# SCH_Mouse-pad_2025-08-08.net
KiCad netlist of a schematic drawn in EasyEDA
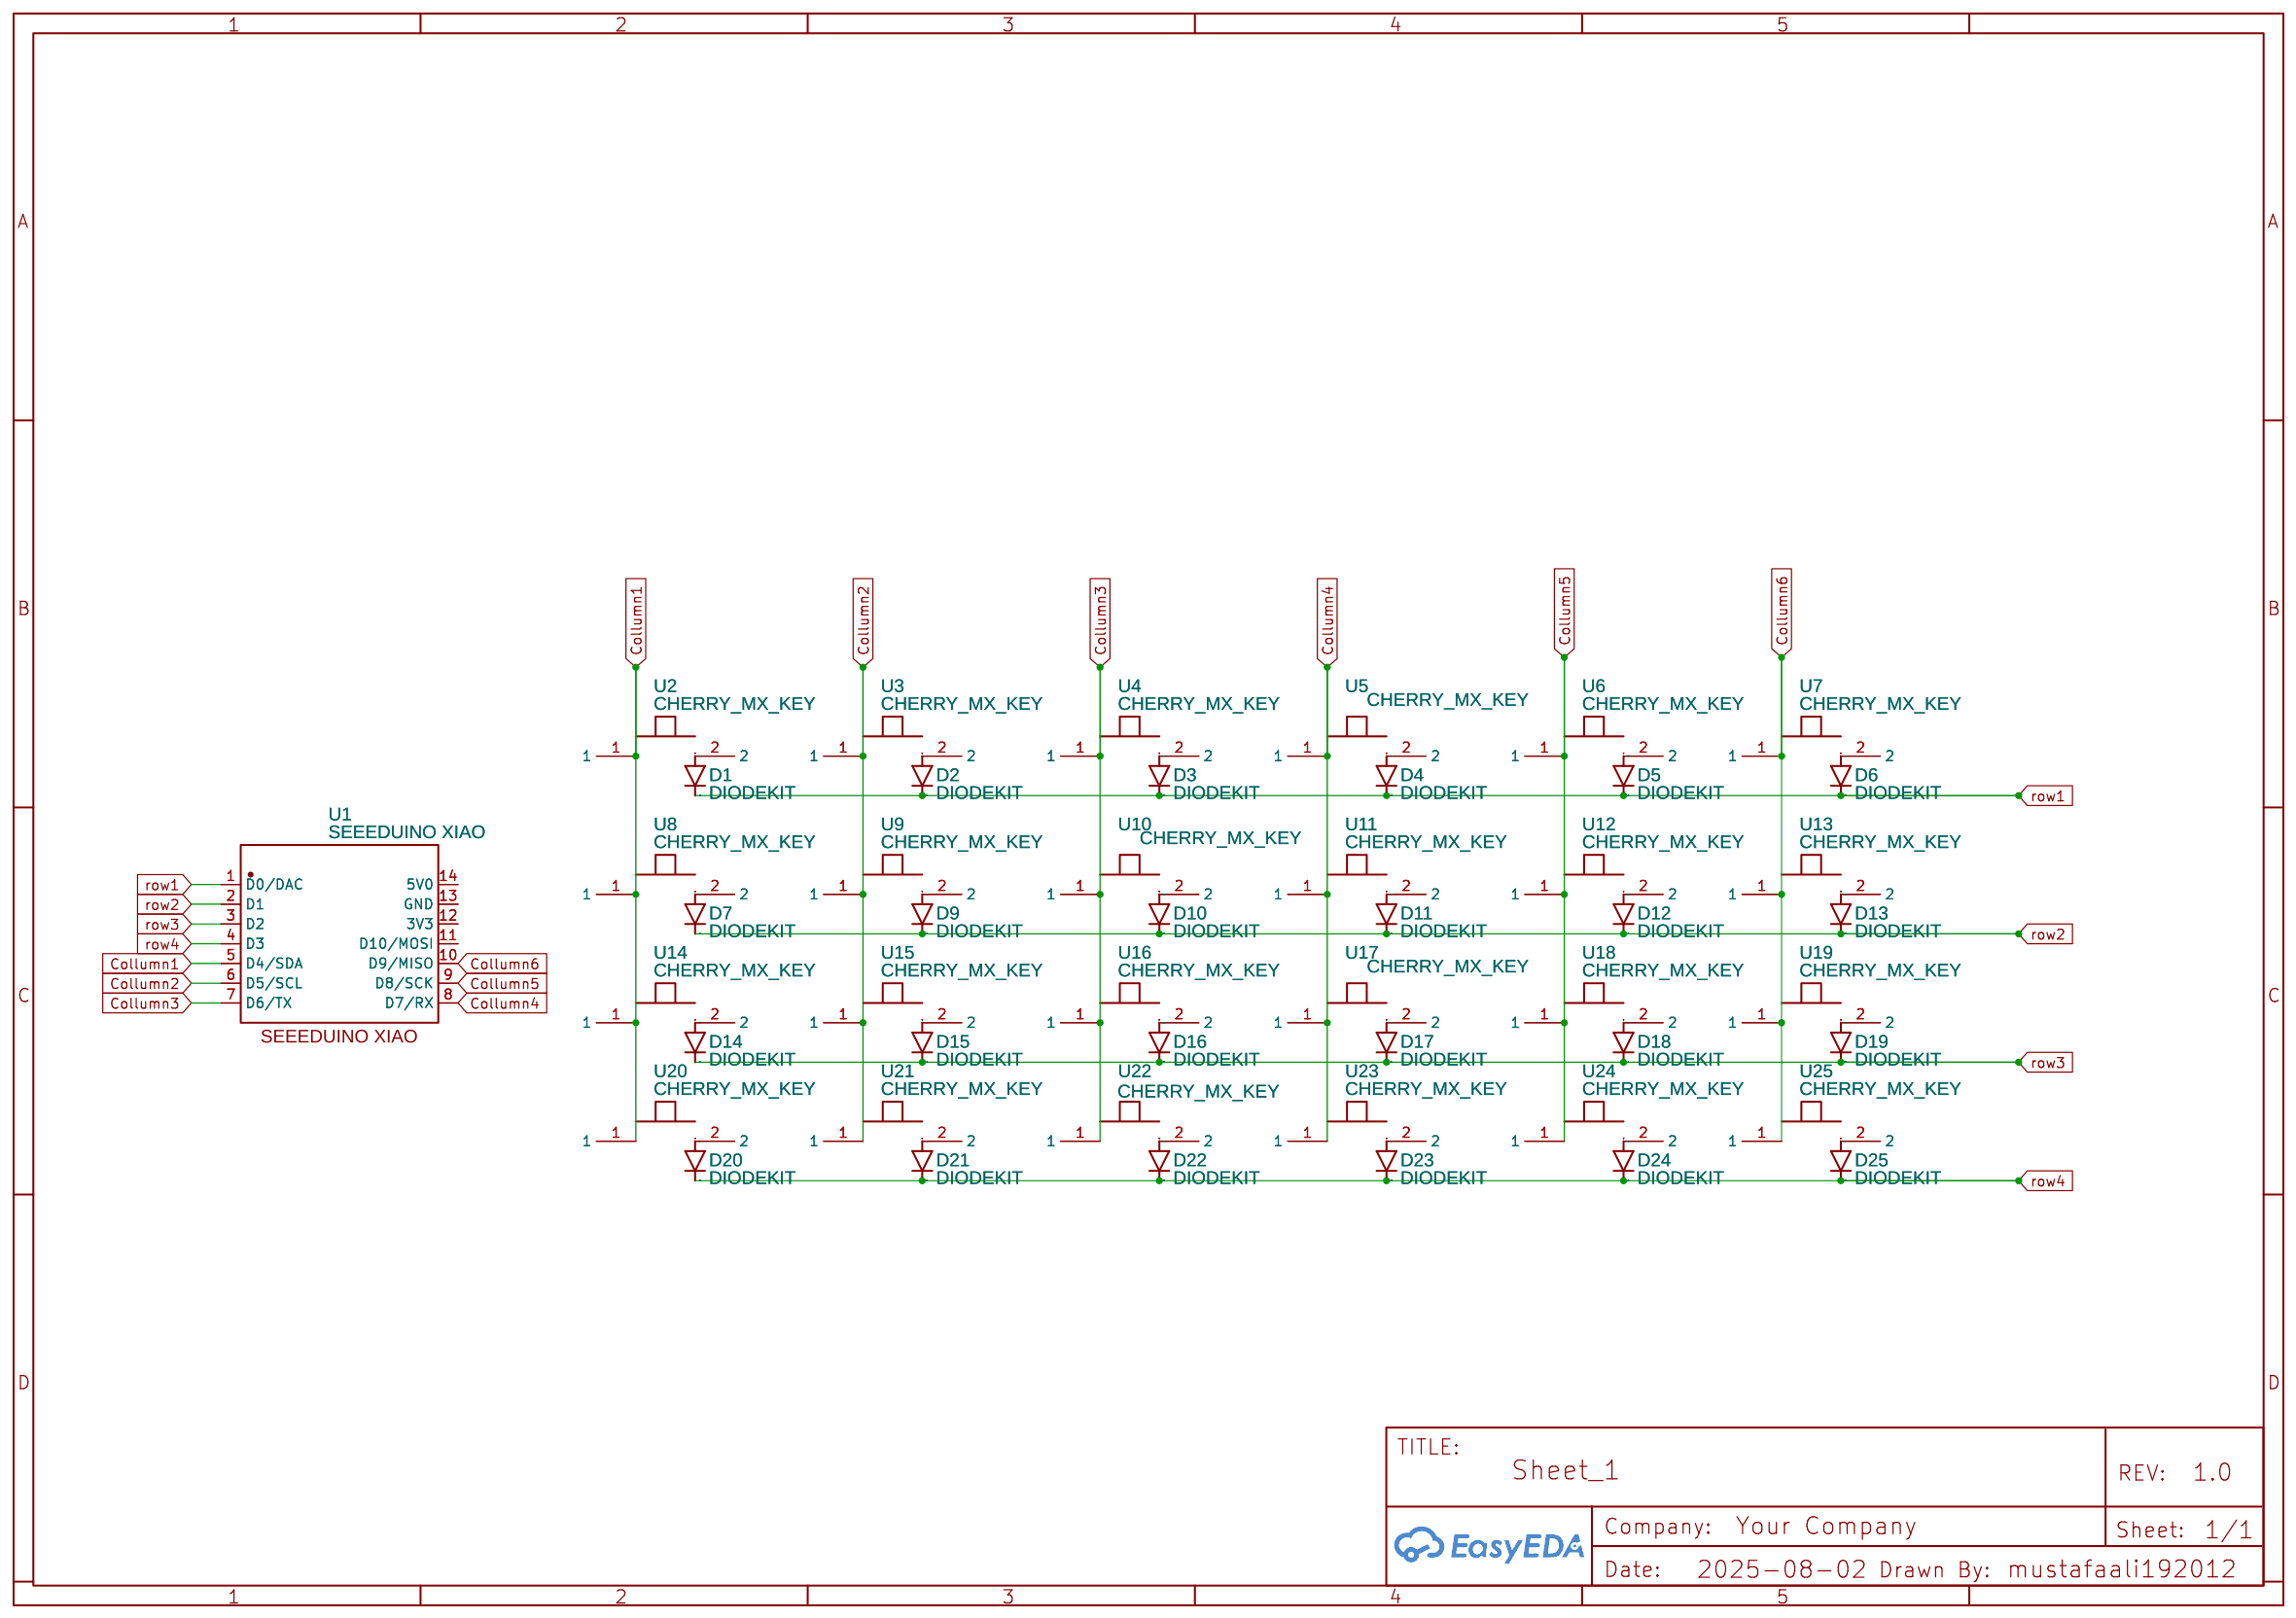
[diagram p0: schematic sheet]

(export (version "E")
  (design (tool "Eeschema 10.0.6"))
  (components
    (comp (ref "D1") (value "DIODEKIT") (libsource (lib "") (part "DIODEKIT")))
    (comp (ref "D2") (value "DIODEKIT") (libsource (lib "") (part "DIODEKIT")))
    (comp (ref "D3") (value "DIODEKIT") (libsource (lib "") (part "DIODEKIT")))
    (comp (ref "D4") (value "DIODEKIT") (libsource (lib "") (part "DIODEKIT")))
    (comp (ref "D5") (value "DIODEKIT") (libsource (lib "") (part "DIODEKIT")))
    (comp (ref "D6") (value "DIODEKIT") (libsource (lib "") (part "DIODEKIT")))
    (comp (ref "D7") (value "DIODEKIT") (libsource (lib "") (part "DIODEKIT")))
    (comp (ref "D9") (value "DIODEKIT") (libsource (lib "") (part "DIODEKIT")))
    (comp (ref "D10") (value "DIODEKIT") (libsource (lib "") (part "DIODEKIT")))
    (comp (ref "D11") (value "DIODEKIT") (libsource (lib "") (part "DIODEKIT")))
    (comp (ref "D12") (value "DIODEKIT") (libsource (lib "") (part "DIODEKIT")))
    (comp (ref "D13") (value "DIODEKIT") (libsource (lib "") (part "DIODEKIT")))
    (comp (ref "D14") (value "DIODEKIT") (libsource (lib "") (part "DIODEKIT")))
    (comp (ref "D15") (value "DIODEKIT") (libsource (lib "") (part "DIODEKIT")))
    (comp (ref "D16") (value "DIODEKIT") (libsource (lib "") (part "DIODEKIT")))
    (comp (ref "D17") (value "DIODEKIT") (libsource (lib "") (part "DIODEKIT")))
    (comp (ref "D18") (value "DIODEKIT") (libsource (lib "") (part "DIODEKIT")))
    (comp (ref "D19") (value "DIODEKIT") (libsource (lib "") (part "DIODEKIT")))
    (comp (ref "D20") (value "DIODEKIT") (libsource (lib "") (part "DIODEKIT")))
    (comp (ref "D21") (value "DIODEKIT") (libsource (lib "") (part "DIODEKIT")))
    (comp (ref "D22") (value "DIODEKIT") (libsource (lib "") (part "DIODEKIT")))
    (comp (ref "D23") (value "DIODEKIT") (libsource (lib "") (part "DIODEKIT")))
    (comp (ref "D24") (value "DIODEKIT") (libsource (lib "") (part "DIODEKIT")))
    (comp (ref "D25") (value "DIODEKIT") (libsource (lib "") (part "DIODEKIT")))
    (comp (ref "U1")
      (value "SEEEDUINO XIAO")
      (fields (field (name "Manufacturer") "Seeeduino"))
      (libsource (lib "") (part "SEEEDUINO XIAO"))
    )
    (comp (ref "U2") (value "CHERRY_MX_KEY") (libsource (lib "") (part "CHERRY_MX_KEY")))
    (comp (ref "U3") (value "CHERRY_MX_KEY") (libsource (lib "") (part "CHERRY_MX_KEY")))
    (comp (ref "U4") (value "CHERRY_MX_KEY") (libsource (lib "") (part "CHERRY_MX_KEY")))
    (comp (ref "U5") (value "CHERRY_MX_KEY") (libsource (lib "") (part "CHERRY_MX_KEY")))
    (comp (ref "U6") (value "CHERRY_MX_KEY") (libsource (lib "") (part "CHERRY_MX_KEY")))
    (comp (ref "U7") (value "CHERRY_MX_KEY") (libsource (lib "") (part "CHERRY_MX_KEY")))
    (comp (ref "U8") (value "CHERRY_MX_KEY") (libsource (lib "") (part "CHERRY_MX_KEY")))
    (comp (ref "U9") (value "CHERRY_MX_KEY") (libsource (lib "") (part "CHERRY_MX_KEY")))
    (comp (ref "U10") (value "CHERRY_MX_KEY") (libsource (lib "") (part "CHERRY_MX_KEY")))
    (comp (ref "U11") (value "CHERRY_MX_KEY") (libsource (lib "") (part "CHERRY_MX_KEY")))
    (comp (ref "U12") (value "CHERRY_MX_KEY") (libsource (lib "") (part "CHERRY_MX_KEY")))
    (comp (ref "U13") (value "CHERRY_MX_KEY") (libsource (lib "") (part "CHERRY_MX_KEY")))
    (comp (ref "U14") (value "CHERRY_MX_KEY") (libsource (lib "") (part "CHERRY_MX_KEY")))
    (comp (ref "U15") (value "CHERRY_MX_KEY") (libsource (lib "") (part "CHERRY_MX_KEY")))
    (comp (ref "U16") (value "CHERRY_MX_KEY") (libsource (lib "") (part "CHERRY_MX_KEY")))
    (comp (ref "U17") (value "CHERRY_MX_KEY") (libsource (lib "") (part "CHERRY_MX_KEY")))
    (comp (ref "U18") (value "CHERRY_MX_KEY") (libsource (lib "") (part "CHERRY_MX_KEY")))
    (comp (ref "U19") (value "CHERRY_MX_KEY") (libsource (lib "") (part "CHERRY_MX_KEY")))
    (comp (ref "U20") (value "CHERRY_MX_KEY") (libsource (lib "") (part "CHERRY_MX_KEY")))
    (comp (ref "U21") (value "CHERRY_MX_KEY") (libsource (lib "") (part "CHERRY_MX_KEY")))
    (comp (ref "U22") (value "CHERRY_MX_KEY") (libsource (lib "") (part "CHERRY_MX_KEY")))
    (comp (ref "U23") (value "CHERRY_MX_KEY") (libsource (lib "") (part "CHERRY_MX_KEY")))
    (comp (ref "U24") (value "CHERRY_MX_KEY") (libsource (lib "") (part "CHERRY_MX_KEY")))
    (comp (ref "U25") (value "CHERRY_MX_KEY") (libsource (lib "") (part "CHERRY_MX_KEY")))
  )
  (nets
    (net (code "1") (name "Collumn1") (class "Default")
      (node (ref "U1") (pin "5") (pinfunction "D4/SDA_5") (pintype "unspecified"))
      (node (ref "U14") (pin "1") (pinfunction "1_1") (pintype "unspecified"))
      (node (ref "U2") (pin "1") (pinfunction "1_1") (pintype "unspecified"))
      (node (ref "U20") (pin "1") (pinfunction "1_1") (pintype "unspecified"))
      (node (ref "U8") (pin "1") (pinfunction "1_1") (pintype "unspecified"))
    )
    (net (code "2") (name "Collumn2") (class "Default")
      (node (ref "U1") (pin "6") (pinfunction "D5/SCL_6") (pintype "unspecified"))
      (node (ref "U15") (pin "1") (pinfunction "1_1") (pintype "unspecified"))
      (node (ref "U21") (pin "1") (pinfunction "1_1") (pintype "unspecified"))
      (node (ref "U3") (pin "1") (pinfunction "1_1") (pintype "unspecified"))
      (node (ref "U9") (pin "1") (pinfunction "1_1") (pintype "unspecified"))
    )
    (net (code "3") (name "Collumn3") (class "Default")
      (node (ref "U1") (pin "7") (pinfunction "D6/TX_7") (pintype "unspecified"))
      (node (ref "U10") (pin "1") (pinfunction "1_1") (pintype "unspecified"))
      (node (ref "U16") (pin "1") (pinfunction "1_1") (pintype "unspecified"))
      (node (ref "U22") (pin "1") (pinfunction "1_1") (pintype "unspecified"))
      (node (ref "U4") (pin "1") (pinfunction "1_1") (pintype "unspecified"))
    )
    (net (code "4") (name "Collumn4") (class "Default")
      (node (ref "U1") (pin "8") (pinfunction "D7/RX_8") (pintype "unspecified"))
      (node (ref "U11") (pin "1") (pinfunction "1_1") (pintype "unspecified"))
      (node (ref "U17") (pin "1") (pinfunction "1_1") (pintype "unspecified"))
      (node (ref "U23") (pin "1") (pinfunction "1_1") (pintype "unspecified"))
      (node (ref "U5") (pin "1") (pinfunction "1_1") (pintype "unspecified"))
    )
    (net (code "5") (name "Collumn5") (class "Default")
      (node (ref "U1") (pin "9") (pinfunction "D8/SCK_9") (pintype "unspecified"))
      (node (ref "U12") (pin "1") (pinfunction "1_1") (pintype "unspecified"))
      (node (ref "U18") (pin "1") (pinfunction "1_1") (pintype "unspecified"))
      (node (ref "U24") (pin "1") (pinfunction "1_1") (pintype "unspecified"))
      (node (ref "U6") (pin "1") (pinfunction "1_1") (pintype "unspecified"))
    )
    (net (code "6") (name "Collumn6") (class "Default")
      (node (ref "U1") (pin "10") (pinfunction "D9/MISO_10") (pintype "unspecified"))
      (node (ref "U13") (pin "1") (pinfunction "1_1") (pintype "unspecified"))
      (node (ref "U19") (pin "1") (pinfunction "1_1") (pintype "unspecified"))
      (node (ref "U25") (pin "1") (pinfunction "1_1") (pintype "unspecified"))
      (node (ref "U7") (pin "1") (pinfunction "1_1") (pintype "unspecified"))
    )
    (net (code "7") (name "Net-(D1-PadA)") (class "Default")
      (node (ref "D1") (pin "A") (pinfunction "A_A") (pintype "bidirectional"))
      (node (ref "U2") (pin "2") (pinfunction "2_2") (pintype "unspecified"))
    )
    (net (code "8") (name "Net-(D2-PadA)") (class "Default")
      (node (ref "D2") (pin "A") (pinfunction "A_A") (pintype "bidirectional"))
      (node (ref "U3") (pin "2") (pinfunction "2_2") (pintype "unspecified"))
    )
    (net (code "9") (name "Net-(D3-PadA)") (class "Default")
      (node (ref "D3") (pin "A") (pinfunction "A_A") (pintype "bidirectional"))
      (node (ref "U4") (pin "2") (pinfunction "2_2") (pintype "unspecified"))
    )
    (net (code "10") (name "Net-(D4-PadA)") (class "Default")
      (node (ref "D4") (pin "A") (pinfunction "A_A") (pintype "bidirectional"))
      (node (ref "U5") (pin "2") (pinfunction "2_2") (pintype "unspecified"))
    )
    (net (code "11") (name "Net-(D5-PadA)") (class "Default")
      (node (ref "D5") (pin "A") (pinfunction "A_A") (pintype "bidirectional"))
      (node (ref "U6") (pin "2") (pinfunction "2_2") (pintype "unspecified"))
    )
    (net (code "12") (name "Net-(D6-PadA)") (class "Default")
      (node (ref "D6") (pin "A") (pinfunction "A_A") (pintype "bidirectional"))
      (node (ref "U7") (pin "2") (pinfunction "2_2") (pintype "unspecified"))
    )
    (net (code "13") (name "Net-(D7-PadA)") (class "Default")
      (node (ref "D7") (pin "A") (pinfunction "A_A") (pintype "bidirectional"))
      (node (ref "U8") (pin "2") (pinfunction "2_2") (pintype "unspecified"))
    )
    (net (code "14") (name "Net-(D9-PadA)") (class "Default")
      (node (ref "D9") (pin "A") (pinfunction "A_A") (pintype "bidirectional"))
      (node (ref "U9") (pin "2") (pinfunction "2_2") (pintype "unspecified"))
    )
    (net (code "15") (name "Net-(D10-PadA)") (class "Default")
      (node (ref "D10") (pin "A") (pinfunction "A_A") (pintype "bidirectional"))
      (node (ref "U10") (pin "2") (pinfunction "2_2") (pintype "unspecified"))
    )
    (net (code "16") (name "Net-(D11-PadA)") (class "Default")
      (node (ref "D11") (pin "A") (pinfunction "A_A") (pintype "bidirectional"))
      (node (ref "U11") (pin "2") (pinfunction "2_2") (pintype "unspecified"))
    )
    (net (code "17") (name "Net-(D12-PadA)") (class "Default")
      (node (ref "D12") (pin "A") (pinfunction "A_A") (pintype "bidirectional"))
      (node (ref "U12") (pin "2") (pinfunction "2_2") (pintype "unspecified"))
    )
    (net (code "18") (name "Net-(D13-PadA)") (class "Default")
      (node (ref "D13") (pin "A") (pinfunction "A_A") (pintype "bidirectional"))
      (node (ref "U13") (pin "2") (pinfunction "2_2") (pintype "unspecified"))
    )
    (net (code "19") (name "Net-(D14-PadA)") (class "Default")
      (node (ref "D14") (pin "A") (pinfunction "A_A") (pintype "bidirectional"))
      (node (ref "U14") (pin "2") (pinfunction "2_2") (pintype "unspecified"))
    )
    (net (code "20") (name "Net-(D15-PadA)") (class "Default")
      (node (ref "D15") (pin "A") (pinfunction "A_A") (pintype "bidirectional"))
      (node (ref "U15") (pin "2") (pinfunction "2_2") (pintype "unspecified"))
    )
    (net (code "21") (name "Net-(D16-PadA)") (class "Default")
      (node (ref "D16") (pin "A") (pinfunction "A_A") (pintype "bidirectional"))
      (node (ref "U16") (pin "2") (pinfunction "2_2") (pintype "unspecified"))
    )
    (net (code "22") (name "Net-(D17-PadA)") (class "Default")
      (node (ref "D17") (pin "A") (pinfunction "A_A") (pintype "bidirectional"))
      (node (ref "U17") (pin "2") (pinfunction "2_2") (pintype "unspecified"))
    )
    (net (code "23") (name "Net-(D18-PadA)") (class "Default")
      (node (ref "D18") (pin "A") (pinfunction "A_A") (pintype "bidirectional"))
      (node (ref "U18") (pin "2") (pinfunction "2_2") (pintype "unspecified"))
    )
    (net (code "24") (name "Net-(D19-PadA)") (class "Default")
      (node (ref "D19") (pin "A") (pinfunction "A_A") (pintype "bidirectional"))
      (node (ref "U19") (pin "2") (pinfunction "2_2") (pintype "unspecified"))
    )
    (net (code "25") (name "Net-(D20-PadA)") (class "Default")
      (node (ref "D20") (pin "A") (pinfunction "A_A") (pintype "bidirectional"))
      (node (ref "U20") (pin "2") (pinfunction "2_2") (pintype "unspecified"))
    )
    (net (code "26") (name "Net-(D21-PadA)") (class "Default")
      (node (ref "D21") (pin "A") (pinfunction "A_A") (pintype "bidirectional"))
      (node (ref "U21") (pin "2") (pinfunction "2_2") (pintype "unspecified"))
    )
    (net (code "27") (name "Net-(D22-PadA)") (class "Default")
      (node (ref "D22") (pin "A") (pinfunction "A_A") (pintype "bidirectional"))
      (node (ref "U22") (pin "2") (pinfunction "2_2") (pintype "unspecified"))
    )
    (net (code "28") (name "Net-(D23-PadA)") (class "Default")
      (node (ref "D23") (pin "A") (pinfunction "A_A") (pintype "bidirectional"))
      (node (ref "U23") (pin "2") (pinfunction "2_2") (pintype "unspecified"))
    )
    (net (code "29") (name "Net-(D24-PadA)") (class "Default")
      (node (ref "D24") (pin "A") (pinfunction "A_A") (pintype "bidirectional"))
      (node (ref "U24") (pin "2") (pinfunction "2_2") (pintype "unspecified"))
    )
    (net (code "30") (name "Net-(D25-PadA)") (class "Default")
      (node (ref "D25") (pin "A") (pinfunction "A_A") (pintype "bidirectional"))
      (node (ref "U25") (pin "2") (pinfunction "2_2") (pintype "unspecified"))
    )
    (net (code "31") (name "row1") (class "Default")
      (node (ref "D1") (pin "C") (pinfunction "C_C") (pintype "bidirectional"))
      (node (ref "D2") (pin "C") (pinfunction "C_C") (pintype "bidirectional"))
      (node (ref "D3") (pin "C") (pinfunction "C_C") (pintype "bidirectional"))
      (node (ref "D4") (pin "C") (pinfunction "C_C") (pintype "bidirectional"))
      (node (ref "D5") (pin "C") (pinfunction "C_C") (pintype "bidirectional"))
      (node (ref "D6") (pin "C") (pinfunction "C_C") (pintype "bidirectional"))
      (node (ref "U1") (pin "1") (pinfunction "D0/DAC_1") (pintype "unspecified"))
    )
    (net (code "32") (name "row2") (class "Default")
      (node (ref "D10") (pin "C") (pinfunction "C_C") (pintype "bidirectional"))
      (node (ref "D11") (pin "C") (pinfunction "C_C") (pintype "bidirectional"))
      (node (ref "D12") (pin "C") (pinfunction "C_C") (pintype "bidirectional"))
      (node (ref "D13") (pin "C") (pinfunction "C_C") (pintype "bidirectional"))
      (node (ref "D7") (pin "C") (pinfunction "C_C") (pintype "bidirectional"))
      (node (ref "D9") (pin "C") (pinfunction "C_C") (pintype "bidirectional"))
      (node (ref "U1") (pin "2") (pinfunction "D1_2") (pintype "unspecified"))
    )
    (net (code "33") (name "row3") (class "Default")
      (node (ref "D14") (pin "C") (pinfunction "C_C") (pintype "bidirectional"))
      (node (ref "D15") (pin "C") (pinfunction "C_C") (pintype "bidirectional"))
      (node (ref "D16") (pin "C") (pinfunction "C_C") (pintype "bidirectional"))
      (node (ref "D17") (pin "C") (pinfunction "C_C") (pintype "bidirectional"))
      (node (ref "D18") (pin "C") (pinfunction "C_C") (pintype "bidirectional"))
      (node (ref "D19") (pin "C") (pinfunction "C_C") (pintype "bidirectional"))
      (node (ref "U1") (pin "3") (pinfunction "D2_3") (pintype "unspecified"))
    )
    (net (code "34") (name "row4") (class "Default")
      (node (ref "D20") (pin "C") (pinfunction "C_C") (pintype "bidirectional"))
      (node (ref "D21") (pin "C") (pinfunction "C_C") (pintype "bidirectional"))
      (node (ref "D22") (pin "C") (pinfunction "C_C") (pintype "bidirectional"))
      (node (ref "D23") (pin "C") (pinfunction "C_C") (pintype "bidirectional"))
      (node (ref "D24") (pin "C") (pinfunction "C_C") (pintype "bidirectional"))
      (node (ref "D25") (pin "C") (pinfunction "C_C") (pintype "bidirectional"))
      (node (ref "U1") (pin "4") (pinfunction "D3_4") (pintype "unspecified"))
    )
    (net (code "35") (name "unconnected-(U1-3V3-Pad12)") (class "Default")
      (node (ref "U1") (pin "12") (pinfunction "3V3_12") (pintype "unspecified"))
    )
    (net (code "36") (name "unconnected-(U1-5V0-Pad14)") (class "Default")
      (node (ref "U1") (pin "14") (pinfunction "5V0_14") (pintype "unspecified"))
    )
    (net (code "37") (name "unconnected-(U1-D10{slash}MOSI-Pad11)") (class "Default")
      (node (ref "U1") (pin "11") (pinfunction "D10/MOSI_11") (pintype "unspecified"))
    )
    (net (code "38") (name "unconnected-(U1-GND-Pad13)") (class "Default")
      (node (ref "U1") (pin "13") (pinfunction "GND_13") (pintype "unspecified"))
    )
  )
)
